# LM1117SW.net
KiCad netlist of a schematic drawn in EAGLE
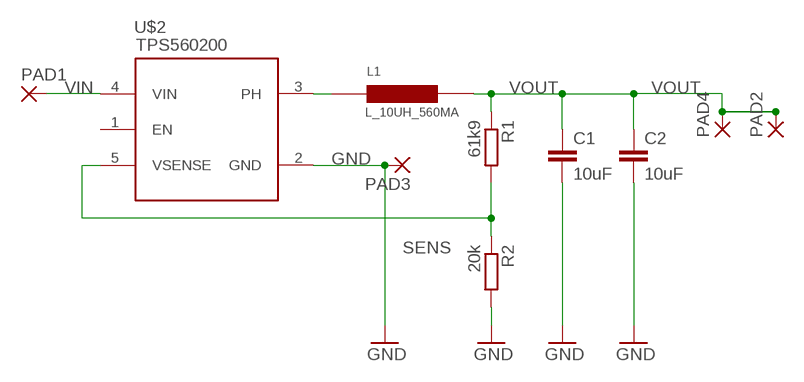
[diagram p0: schematic, sheet 1]

(export (version "E")
  (design (tool "Eeschema 10.0.6"))
  (components
    (comp (ref "C1")
      (value "10uF")
      (footprint "eagle-import:C0805K")
      (fields (field (name "MF") "MULTICOMP") (field (name "MPN") "MC0805X106K250CT"))
      (libsource (lib "eagle-import") (part "C-EUC0805K"))
    )
    (comp (ref "C2")
      (value "10uF")
      (footprint "eagle-import:C0805K")
      (fields (field (name "MF") "MULTICOMP") (field (name "MPN") "MC0805X106K250CT"))
      (libsource (lib "eagle-import") (part "C-EUC0805K"))
    )
    (comp (ref "L1")
      (value "L_10UH_560MA")
      (footprint "eagle-import:TYS3010100M-10")
      (fields (field (name "MF") "LAIRD TECHNOLOGIES") (field (name "MPN") "TYS3010100M-10"))
      (libsource (lib "eagle-import") (part "L_10UH_560MA"))
    )
    (comp (ref "PAD1")
      (value "1,6/0,9")
      (footprint "eagle-import:1,6_0,9")
      (libsource (lib "eagle-import") (part "1,6/0,9"))
    )
    (comp (ref "PAD2")
      (value "1,6/0,9")
      (footprint "eagle-import:1,6_0,9")
      (libsource (lib "eagle-import") (part "1,6/0,9"))
    )
    (comp (ref "PAD3")
      (value "1,6/0,9")
      (footprint "eagle-import:1,6_0,9")
      (libsource (lib "eagle-import") (part "1,6/0,9"))
    )
    (comp (ref "PAD4")
      (value "1,6/0,9")
      (footprint "eagle-import:1,6_0,9")
      (libsource (lib "eagle-import") (part "1,6/0,9"))
    )
    (comp (ref "R1")
      (value "61k9")
      (footprint "eagle-import:R0402")
      (fields (field (name "MF") "MULTICOMP") (field (name "MPN") "MC00625W0402161K9"))
      (libsource (lib "eagle-import") (part "R-EU_R0402"))
    )
    (comp (ref "R2")
      (value "20k")
      (footprint "eagle-import:R0402")
      (fields (field (name "MF") "VISHAY DRALORIC") (field (name "MPN") "CRCW040220K0FKED"))
      (libsource (lib "eagle-import") (part "R-EU_R0402"))
    )
    (comp (ref "U$2")
      (value "TPS560200")
      (footprint "eagle-import:SOT23-5")
      (fields (field (name "MF") "TEXAS INSTRUMENTS") (field (name "MPN") "TPS560200DBVT"))
      (libsource (lib "eagle-import") (part "TPS560200"))
    )
  )
  (nets
    (net (code "1") (name "/SENS") (class "Default")
      (node (ref "R1") (pin "2") (pinfunction "2_2") (pintype "passive"))
      (node (ref "R2") (pin "1") (pinfunction "1_1") (pintype "passive"))
      (node (ref "U$2") (pin "5") (pinfunction "VSENSE_5") (pintype "bidirectional"))
    )
    (net (code "2") (name "/VIN") (class "Default")
      (node (ref "PAD1") (pin "1") (pinfunction "P_1") (pintype "passive"))
      (node (ref "U$2") (pin "4") (pinfunction "VIN_4") (pintype "bidirectional"))
    )
    (net (code "3") (name "/VOUT") (class "Default")
      (node (ref "C1") (pin "1") (pinfunction "1_1") (pintype "passive"))
      (node (ref "C2") (pin "1") (pinfunction "1_1") (pintype "passive"))
      (node (ref "L1") (pin "P$2") (pinfunction "P$2_P$2") (pintype "bidirectional"))
      (node (ref "PAD2") (pin "1") (pinfunction "P_1") (pintype "passive"))
      (node (ref "PAD4") (pin "1") (pinfunction "P_1") (pintype "passive"))
      (node (ref "R1") (pin "1") (pinfunction "1_1") (pintype "passive"))
    )
    (net (code "4") (name "GND") (class "Default")
      (node (ref "C1") (pin "2") (pinfunction "2_2") (pintype "passive"))
      (node (ref "C2") (pin "2") (pinfunction "2_2") (pintype "passive"))
      (node (ref "PAD3") (pin "1") (pinfunction "P_1") (pintype "passive"))
      (node (ref "R2") (pin "2") (pinfunction "2_2") (pintype "passive"))
      (node (ref "U$2") (pin "2") (pinfunction "GND_2") (pintype "bidirectional"))
    )
    (net (code "5") (name "Net-(U$2-PH)") (class "Default")
      (node (ref "L1") (pin "P$1") (pinfunction "P$1_P$1") (pintype "bidirectional"))
      (node (ref "U$2") (pin "3") (pinfunction "PH_3") (pintype "bidirectional"))
    )
    (net (code "6") (name "unconnected-(U$2-EN-Pad1)") (class "Default")
      (node (ref "U$2") (pin "1") (pinfunction "EN_1") (pintype "bidirectional"))
    )
  )
)
